# xlrpcb.net
KiCad netlist of a schematic drawn in EAGLE
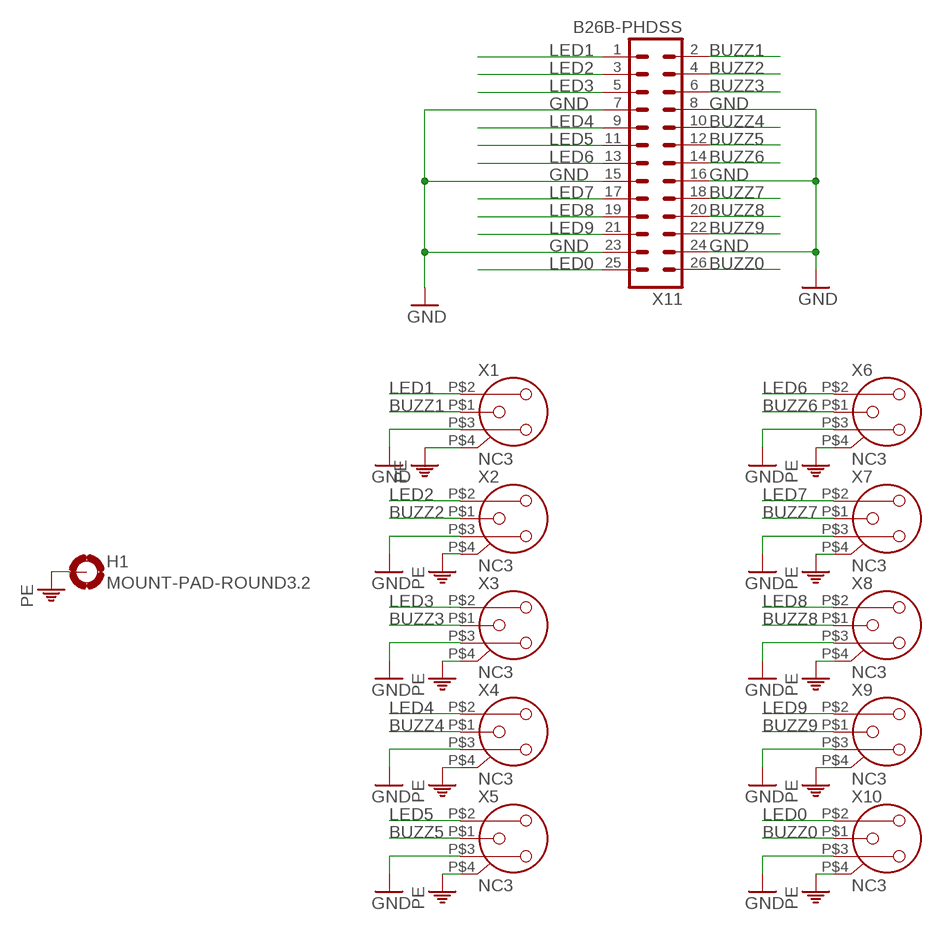
[diagram p0: schematic, sheet 1]

(export (version "E")
  (design (tool "Eeschema 10.0.6"))
  (components
    (comp (ref "H1")
      (value "MOUNT-PAD-ROUND3.2")
      (footprint "eagle-import:3,2-PAD")
      (libsource (lib "eagle-import") (part "MOUNT-PAD-ROUND3.2"))
    )
    (comp (ref "X1")
      (value "NC3")
      (footprint "eagle-import:NC3FD-X")
      (libsource (lib "eagle-import") (part "NC3"))
    )
    (comp (ref "X2")
      (value "NC3")
      (footprint "eagle-import:NC3FD-X")
      (libsource (lib "eagle-import") (part "NC3"))
    )
    (comp (ref "X3")
      (value "NC3")
      (footprint "eagle-import:NC3FD-X")
      (libsource (lib "eagle-import") (part "NC3"))
    )
    (comp (ref "X4")
      (value "NC3")
      (footprint "eagle-import:NC3FD-X")
      (libsource (lib "eagle-import") (part "NC3"))
    )
    (comp (ref "X5")
      (value "NC3")
      (footprint "eagle-import:NC3FD-X")
      (libsource (lib "eagle-import") (part "NC3"))
    )
    (comp (ref "X6")
      (value "NC3")
      (footprint "eagle-import:NC3FD-X")
      (libsource (lib "eagle-import") (part "NC3"))
    )
    (comp (ref "X7")
      (value "NC3")
      (footprint "eagle-import:NC3FD-X")
      (libsource (lib "eagle-import") (part "NC3"))
    )
    (comp (ref "X8")
      (value "NC3")
      (footprint "eagle-import:NC3FD-X")
      (libsource (lib "eagle-import") (part "NC3"))
    )
    (comp (ref "X9")
      (value "NC3")
      (footprint "eagle-import:NC3FD-X")
      (libsource (lib "eagle-import") (part "NC3"))
    )
    (comp (ref "X10")
      (value "NC3")
      (footprint "eagle-import:NC3FD-X")
      (libsource (lib "eagle-import") (part "NC3"))
    )
    (comp (ref "X11")
      (value "B26B-PHDSS")
      (footprint "eagle-import:B26B-PHDSS")
      (libsource (lib "eagle-import") (part "B26B-PHDSS"))
    )
  )
  (nets
    (net (code "1") (name "/BUZZ0") (class "Default")
      (node (ref "X10") (pin "P$1") (pinfunction "3_P$1") (pintype "passive"))
      (node (ref "X11") (pin "26") (pinfunction "26_26") (pintype "passive"))
    )
    (net (code "2") (name "/BUZZ1") (class "Default")
      (node (ref "X1") (pin "P$1") (pinfunction "3_P$1") (pintype "passive"))
      (node (ref "X11") (pin "2") (pinfunction "2_2") (pintype "passive"))
    )
    (net (code "3") (name "/BUZZ2") (class "Default")
      (node (ref "X11") (pin "4") (pinfunction "4_4") (pintype "passive"))
      (node (ref "X2") (pin "P$1") (pinfunction "3_P$1") (pintype "passive"))
    )
    (net (code "4") (name "/BUZZ3") (class "Default")
      (node (ref "X11") (pin "6") (pinfunction "6_6") (pintype "passive"))
      (node (ref "X3") (pin "P$1") (pinfunction "3_P$1") (pintype "passive"))
    )
    (net (code "5") (name "/BUZZ4") (class "Default")
      (node (ref "X11") (pin "10") (pinfunction "10_10") (pintype "passive"))
      (node (ref "X4") (pin "P$1") (pinfunction "3_P$1") (pintype "passive"))
    )
    (net (code "6") (name "/BUZZ5") (class "Default")
      (node (ref "X11") (pin "12") (pinfunction "12_12") (pintype "passive"))
      (node (ref "X5") (pin "P$1") (pinfunction "3_P$1") (pintype "passive"))
    )
    (net (code "7") (name "/BUZZ6") (class "Default")
      (node (ref "X11") (pin "14") (pinfunction "14_14") (pintype "passive"))
      (node (ref "X6") (pin "P$1") (pinfunction "3_P$1") (pintype "passive"))
    )
    (net (code "8") (name "/BUZZ7") (class "Default")
      (node (ref "X11") (pin "18") (pinfunction "18_18") (pintype "passive"))
      (node (ref "X7") (pin "P$1") (pinfunction "3_P$1") (pintype "passive"))
    )
    (net (code "9") (name "/BUZZ8") (class "Default")
      (node (ref "X11") (pin "20") (pinfunction "20_20") (pintype "passive"))
      (node (ref "X8") (pin "P$1") (pinfunction "3_P$1") (pintype "passive"))
    )
    (net (code "10") (name "/BUZZ9") (class "Default")
      (node (ref "X11") (pin "22") (pinfunction "22_22") (pintype "passive"))
      (node (ref "X9") (pin "P$1") (pinfunction "3_P$1") (pintype "passive"))
    )
    (net (code "11") (name "/LED0") (class "Default")
      (node (ref "X10") (pin "P$2") (pinfunction "1_P$2") (pintype "passive"))
      (node (ref "X11") (pin "25") (pinfunction "25_25") (pintype "passive"))
    )
    (net (code "12") (name "/LED1") (class "Default")
      (node (ref "X1") (pin "P$2") (pinfunction "1_P$2") (pintype "passive"))
      (node (ref "X11") (pin "1") (pinfunction "1_1") (pintype "passive"))
    )
    (net (code "13") (name "/LED2") (class "Default")
      (node (ref "X11") (pin "3") (pinfunction "3_3") (pintype "passive"))
      (node (ref "X2") (pin "P$2") (pinfunction "1_P$2") (pintype "passive"))
    )
    (net (code "14") (name "/LED3") (class "Default")
      (node (ref "X11") (pin "5") (pinfunction "5_5") (pintype "passive"))
      (node (ref "X3") (pin "P$2") (pinfunction "1_P$2") (pintype "passive"))
    )
    (net (code "15") (name "/LED4") (class "Default")
      (node (ref "X11") (pin "9") (pinfunction "9_9") (pintype "passive"))
      (node (ref "X4") (pin "P$2") (pinfunction "1_P$2") (pintype "passive"))
    )
    (net (code "16") (name "/LED5") (class "Default")
      (node (ref "X11") (pin "11") (pinfunction "11_11") (pintype "passive"))
      (node (ref "X5") (pin "P$2") (pinfunction "1_P$2") (pintype "passive"))
    )
    (net (code "17") (name "/LED6") (class "Default")
      (node (ref "X11") (pin "13") (pinfunction "13_13") (pintype "passive"))
      (node (ref "X6") (pin "P$2") (pinfunction "1_P$2") (pintype "passive"))
    )
    (net (code "18") (name "/LED7") (class "Default")
      (node (ref "X11") (pin "17") (pinfunction "17_17") (pintype "passive"))
      (node (ref "X7") (pin "P$2") (pinfunction "1_P$2") (pintype "passive"))
    )
    (net (code "19") (name "/LED8") (class "Default")
      (node (ref "X11") (pin "19") (pinfunction "19_19") (pintype "passive"))
      (node (ref "X8") (pin "P$2") (pinfunction "1_P$2") (pintype "passive"))
    )
    (net (code "20") (name "/LED9") (class "Default")
      (node (ref "X11") (pin "21") (pinfunction "21_21") (pintype "passive"))
      (node (ref "X9") (pin "P$2") (pinfunction "1_P$2") (pintype "passive"))
    )
    (net (code "21") (name "GND") (class "Default")
      (node (ref "X1") (pin "P$3") (pinfunction "2_P$3") (pintype "passive"))
      (node (ref "X10") (pin "P$3") (pinfunction "2_P$3") (pintype "passive"))
      (node (ref "X11") (pin "15") (pinfunction "15_15") (pintype "passive"))
      (node (ref "X11") (pin "16") (pinfunction "16_16") (pintype "passive"))
      (node (ref "X11") (pin "23") (pinfunction "23_23") (pintype "passive"))
      (node (ref "X11") (pin "24") (pinfunction "24_24") (pintype "passive"))
      (node (ref "X11") (pin "7") (pinfunction "7_7") (pintype "passive"))
      (node (ref "X11") (pin "8") (pinfunction "8_8") (pintype "passive"))
      (node (ref "X2") (pin "P$3") (pinfunction "2_P$3") (pintype "passive"))
      (node (ref "X3") (pin "P$3") (pinfunction "2_P$3") (pintype "passive"))
      (node (ref "X4") (pin "P$3") (pinfunction "2_P$3") (pintype "passive"))
      (node (ref "X5") (pin "P$3") (pinfunction "2_P$3") (pintype "passive"))
      (node (ref "X6") (pin "P$3") (pinfunction "2_P$3") (pintype "passive"))
      (node (ref "X7") (pin "P$3") (pinfunction "2_P$3") (pintype "passive"))
      (node (ref "X8") (pin "P$3") (pinfunction "2_P$3") (pintype "passive"))
      (node (ref "X9") (pin "P$3") (pinfunction "2_P$3") (pintype "passive"))
    )
    (net (code "22") (name "PE") (class "Default")
      (node (ref "H1") (pin "B3,2") (pinfunction "MOUNT_B3,2") (pintype "passive"))
      (node (ref "X1") (pin "P$4") (pinfunction "G_P$4") (pintype "passive"))
      (node (ref "X10") (pin "P$4") (pinfunction "G_P$4") (pintype "passive"))
      (node (ref "X2") (pin "P$4") (pinfunction "G_P$4") (pintype "passive"))
      (node (ref "X3") (pin "P$4") (pinfunction "G_P$4") (pintype "passive"))
      (node (ref "X4") (pin "P$4") (pinfunction "G_P$4") (pintype "passive"))
      (node (ref "X5") (pin "P$4") (pinfunction "G_P$4") (pintype "passive"))
      (node (ref "X6") (pin "P$4") (pinfunction "G_P$4") (pintype "passive"))
      (node (ref "X7") (pin "P$4") (pinfunction "G_P$4") (pintype "passive"))
      (node (ref "X8") (pin "P$4") (pinfunction "G_P$4") (pintype "passive"))
      (node (ref "X9") (pin "P$4") (pinfunction "G_P$4") (pintype "passive"))
    )
  )
)
